# hw.net
KiCad netlist of a schematic drawn in EAGLE
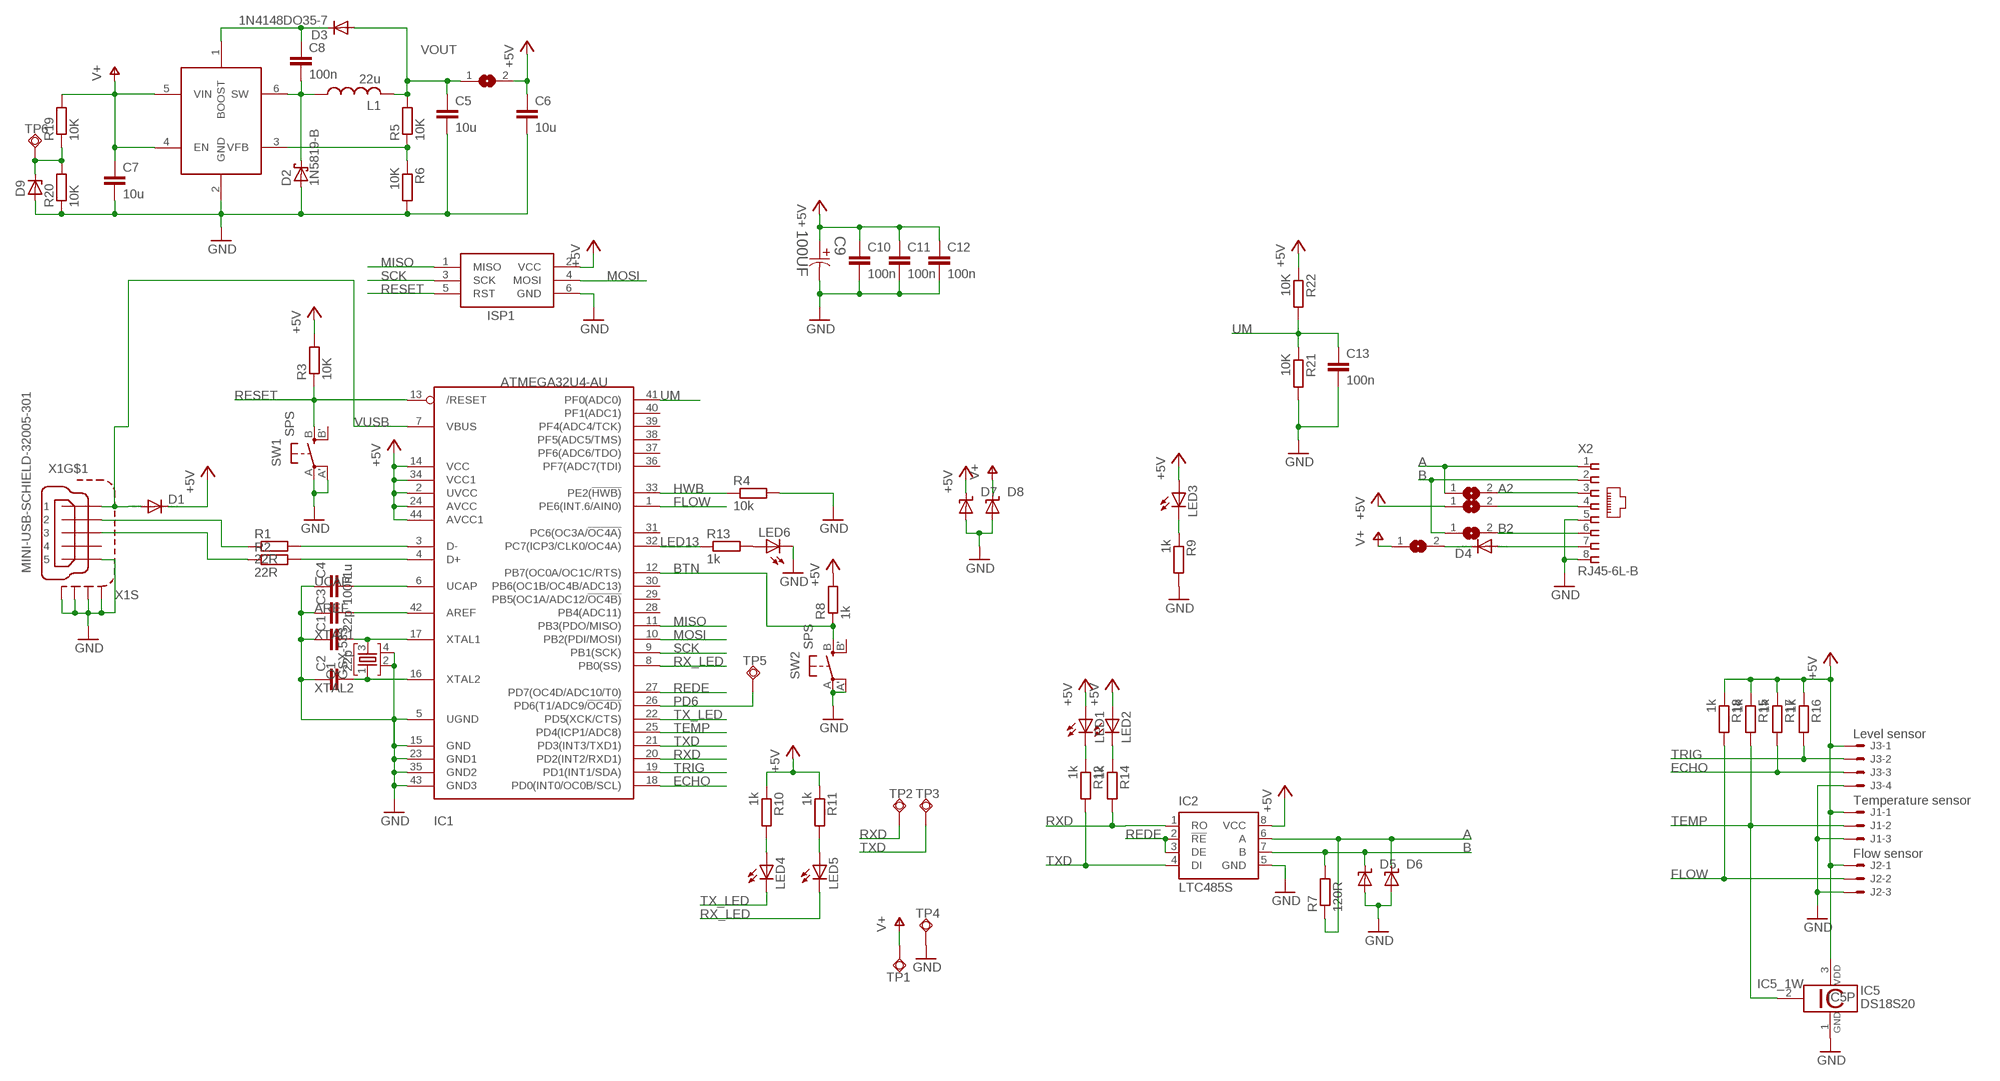
[diagram p0: schematic, sheet 1]

(export (version "E")
  (design (tool "Eeschema 10.0.6"))
  (components
    (comp (ref "C1")
      (value "22p")
      (footprint "eagle-import:C0805K")
      (libsource (lib "eagle-import") (part "C-EUC0805K"))
    )
    (comp (ref "C2")
      (value "22p")
      (footprint "eagle-import:C0805K")
      (libsource (lib "eagle-import") (part "C-EUC0805K"))
    )
    (comp (ref "C3")
      (value "100n")
      (footprint "eagle-import:C0805K")
      (libsource (lib "eagle-import") (part "C-EUC0805K"))
    )
    (comp (ref "C4")
      (value "1u")
      (footprint "eagle-import:C0805K")
      (libsource (lib "eagle-import") (part "C-EUC0805K"))
    )
    (comp (ref "C5")
      (value "10u")
      (footprint "eagle-import:C0805K")
      (libsource (lib "eagle-import") (part "C-EUC0805K"))
    )
    (comp (ref "C6")
      (value "10u")
      (footprint "eagle-import:C0805K")
      (libsource (lib "eagle-import") (part "C-EUC0805K"))
    )
    (comp (ref "C7")
      (value "10u")
      (footprint "eagle-import:C0805K")
      (libsource (lib "eagle-import") (part "rcl_334_C-EUC0805K"))
    )
    (comp (ref "C8")
      (value "100n")
      (footprint "eagle-import:C0805K")
      (libsource (lib "eagle-import") (part "C-EUC0805K"))
    )
    (comp (ref "C9")
      (value "100UF")
      (footprint "eagle-import:CAPAE660X610N")
      (fields (field (name "MPN") "EEE-FK0J101AP") (field (name "TOLERANCE") "±20 %"))
      (libsource (lib "eagle-import") (part "EEE--CASE-DFK0J101AP"))
    )
    (comp (ref "C10")
      (value "100n")
      (footprint "eagle-import:C0805K")
      (libsource (lib "eagle-import") (part "C-EUC0805K"))
    )
    (comp (ref "C11")
      (value "100n")
      (footprint "eagle-import:C0805K")
      (libsource (lib "eagle-import") (part "C-EUC0805K"))
    )
    (comp (ref "C12")
      (value "100n")
      (footprint "eagle-import:C0805K")
      (libsource (lib "eagle-import") (part "C-EUC0805K"))
    )
    (comp (ref "C13")
      (value "100n")
      (footprint "eagle-import:C0805K")
      (libsource (lib "eagle-import") (part "C-EUC0805K"))
    )
    (comp (ref "D1")
      (value "DIODE-MICROMELF-W")
      (footprint "eagle-import:MICROMELF-W")
      (libsource (lib "eagle-import") (part "DIODE-MICROMELF-W"))
    )
    (comp (ref "D2")
      (value "1N5819-B")
      (footprint "eagle-import:DO41-7.6")
      (libsource (lib "eagle-import") (part "1N5819-B"))
    )
    (comp (ref "D3")
      (value "1N4148DO35-7")
      (footprint "eagle-import:DO35-7")
      (libsource (lib "eagle-import") (part "1N4148DO35-7"))
    )
    (comp (ref "D4")
      (value "DIODE-MINIMELF")
      (footprint "eagle-import:MINIMELF")
      (libsource (lib "eagle-import") (part "diode_210_DIODE-MINIMELF"))
    )
    (comp (ref "D5")
      (value "SUPPRESSOR-SMBG")
      (footprint "eagle-import:SMBG")
      (libsource (lib "eagle-import") (part "SUPPRESSOR-SMBG"))
    )
    (comp (ref "D6")
      (value "SUPPRESSOR-SMBG")
      (footprint "eagle-import:SMBG")
      (libsource (lib "eagle-import") (part "SUPPRESSOR-SMBG"))
    )
    (comp (ref "D7")
      (value "SUPPRESSOR-SMBG")
      (footprint "eagle-import:SMBG")
      (libsource (lib "eagle-import") (part "SUPPRESSOR-SMBG"))
    )
    (comp (ref "D8")
      (value "SUPPRESSOR-SMBG")
      (footprint "eagle-import:SMBG")
      (libsource (lib "eagle-import") (part "SUPPRESSOR-SMBG"))
    )
    (comp (ref "D9")
      (value "ZENER-DIODESMB")
      (footprint "eagle-import:SMB")
      (libsource (lib "eagle-import") (part "ZENER-DIODESMB"))
    )
    (comp (ref "IC1")
      (value "ATMEGA32U4-AU")
      (footprint "eagle-import:TQFP44")
      (libsource (lib "eagle-import") (part "ATMEGA32U4-AU"))
    )
    (comp (ref "IC2")
      (value "LTC485S")
      (footprint "eagle-import:SOIC8")
      (libsource (lib "eagle-import") (part "LTC485S"))
    )
    (comp (ref "IC3")
      (value "MCP16301/H")
      (footprint "eagle-import:SOT23-6")
      (libsource (lib "eagle-import") (part "MCP16301/H"))
    )
    (comp (ref "IC5")
      (value "DS18S20")
      (footprint "eagle-import:TO92-")
      (fields (field (name "SPICEPREFIX") "X"))
      (libsource (lib "eagle-import") (part "DS18S20"))
    )
    (comp (ref "ISP1")
      (value "AVRISP-6")
      (footprint "eagle-import:AVRISP")
      (libsource (lib "eagle-import") (part "AVRISP-6"))
    )
    (comp (ref "J1")
      (value "Temperature sensor")
      (footprint "eagle-import:6410-03")
      (fields (field (name "MF") "MOLEX"))
      (libsource (lib "eagle-import") (part "22-?-0327-2031"))
    )
    (comp (ref "J2")
      (value "Flow sensor")
      (footprint "eagle-import:6410-03")
      (fields (field (name "MF") "MOLEX"))
      (libsource (lib "eagle-import") (part "22-?-0327-2031"))
    )
    (comp (ref "J3")
      (value "Level sensor")
      (footprint "eagle-import:6410-04")
      (fields (field (name "MF") "MOLEX"))
      (libsource (lib "eagle-import") (part "22-?-0427-2041"))
    )
    (comp (ref "L1")
      (value "22u")
      (footprint "eagle-import:0207_12")
      (libsource (lib "eagle-import") (part "L-US0207/12"))
    )
    (comp (ref "LED1")
      (value "LEDCHIPLED_0805")
      (footprint "eagle-import:CHIPLED_0805")
      (libsource (lib "eagle-import") (part "LEDCHIPLED_0805"))
    )
    (comp (ref "LED2")
      (value "LEDCHIPLED_0805")
      (footprint "eagle-import:CHIPLED_0805")
      (libsource (lib "eagle-import") (part "LEDCHIPLED_0805"))
    )
    (comp (ref "LED3")
      (value "LEDCHIPLED_0805")
      (footprint "eagle-import:CHIPLED_0805")
      (libsource (lib "eagle-import") (part "LEDCHIPLED_0805"))
    )
    (comp (ref "LED4")
      (value "LEDCHIPLED_0805")
      (footprint "eagle-import:CHIPLED_0805")
      (libsource (lib "eagle-import") (part "LEDCHIPLED_0805"))
    )
    (comp (ref "LED5")
      (value "LEDCHIPLED_0805")
      (footprint "eagle-import:CHIPLED_0805")
      (libsource (lib "eagle-import") (part "LEDCHIPLED_0805"))
    )
    (comp (ref "LED6")
      (value "LEDCHIPLED_0805")
      (footprint "eagle-import:CHIPLED_0805")
      (libsource (lib "eagle-import") (part "LEDCHIPLED_0805"))
    )
    (comp (ref "Q1")
      (value "GSX-533")
      (footprint "eagle-import:5032")
      (libsource (lib "eagle-import") (part "GSX-533"))
    )
    (comp (ref "R1")
      (value "22R")
      (footprint "eagle-import:M0805")
      (libsource (lib "eagle-import") (part "R-EU_M0805"))
    )
    (comp (ref "R2")
      (value "22R")
      (footprint "eagle-import:M0805")
      (libsource (lib "eagle-import") (part "R-EU_M0805"))
    )
    (comp (ref "R3")
      (value "10K")
      (footprint "eagle-import:M0805")
      (libsource (lib "eagle-import") (part "R-EU_M0805"))
    )
    (comp (ref "R4")
      (value "10k")
      (footprint "eagle-import:M0805")
      (libsource (lib "eagle-import") (part "R-EU_M0805"))
    )
    (comp (ref "R5")
      (value "10K")
      (footprint "eagle-import:M0805")
      (libsource (lib "eagle-import") (part "R-EU_M0805"))
    )
    (comp (ref "R6")
      (value "10K")
      (footprint "eagle-import:M0805")
      (libsource (lib "eagle-import") (part "R-EU_M0805"))
    )
    (comp (ref "R7")
      (value "120R")
      (footprint "eagle-import:M0805")
      (libsource (lib "eagle-import") (part "R-EU_M0805"))
    )
    (comp (ref "R8")
      (value "1k")
      (footprint "eagle-import:M0805")
      (libsource (lib "eagle-import") (part "R-EU_M0805"))
    )
    (comp (ref "R9")
      (value "1k")
      (footprint "eagle-import:M0805")
      (libsource (lib "eagle-import") (part "R-EU_M0805"))
    )
    (comp (ref "R10")
      (value "1k")
      (footprint "eagle-import:M0805")
      (libsource (lib "eagle-import") (part "R-EU_M0805"))
    )
    (comp (ref "R11")
      (value "1k")
      (footprint "eagle-import:M0805")
      (libsource (lib "eagle-import") (part "R-EU_M0805"))
    )
    (comp (ref "R12")
      (value "1k")
      (footprint "eagle-import:M0805")
      (libsource (lib "eagle-import") (part "R-EU_M0805"))
    )
    (comp (ref "R13")
      (value "1k")
      (footprint "eagle-import:M0805")
      (libsource (lib "eagle-import") (part "R-EU_M0805"))
    )
    (comp (ref "R14")
      (value "1k")
      (footprint "eagle-import:M0805")
      (libsource (lib "eagle-import") (part "R-EU_M0805"))
    )
    (comp (ref "R15")
      (value "1k")
      (footprint "eagle-import:M0805")
      (libsource (lib "eagle-import") (part "R-EU_M0805"))
    )
    (comp (ref "R16")
      (value "1k")
      (footprint "eagle-import:M0805")
      (libsource (lib "eagle-import") (part "R-EU_M0805"))
    )
    (comp (ref "R17")
      (value "1k")
      (footprint "eagle-import:M0805")
      (libsource (lib "eagle-import") (part "R-EU_M0805"))
    )
    (comp (ref "R18")
      (value "1k")
      (footprint "eagle-import:M0805")
      (libsource (lib "eagle-import") (part "R-EU_M0805"))
    )
    (comp (ref "R19")
      (value "10K")
      (footprint "eagle-import:M0805")
      (libsource (lib "eagle-import") (part "R-EU_M0805"))
    )
    (comp (ref "R20")
      (value "10K")
      (footprint "eagle-import:M0805")
      (libsource (lib "eagle-import") (part "R-EU_M0805"))
    )
    (comp (ref "R21")
      (value "10K")
      (footprint "eagle-import:M0805")
      (libsource (lib "eagle-import") (part "R-EU_M0805"))
    )
    (comp (ref "R22")
      (value "10K")
      (footprint "eagle-import:M0805")
      (libsource (lib "eagle-import") (part "R-EU_M0805"))
    )
    (comp (ref "SJ1") (value "SJ") (footprint "eagle-import:SJ") (libsource (lib "eagle-import") (part "SJ")))
    (comp (ref "SJ2") (value "SJ") (footprint "eagle-import:SJ") (libsource (lib "eagle-import") (part "SJ")))
    (comp (ref "SJ3") (value "SJ") (footprint "eagle-import:SJ") (libsource (lib "eagle-import") (part "SJ")))
    (comp (ref "SJ4") (value "SJ") (footprint "eagle-import:SJ") (libsource (lib "eagle-import") (part "SJ")))
    (comp (ref "SJ5") (value "SJ") (footprint "eagle-import:SJ") (libsource (lib "eagle-import") (part "SJ")))
    (comp (ref "SW1")
      (value "SPS")
      (footprint "eagle-import:EVQ-Q2")
      (libsource (lib "eagle-import") (part "SPST_TACT-EVQQ2"))
    )
    (comp (ref "SW2")
      (value "SPS")
      (footprint "eagle-import:EVQ-Q2")
      (libsource (lib "eagle-import") (part "SPST_TACT-EVQQ2"))
    )
    (comp (ref "TP1")
      (value "TPSQTP20SQ")
      (footprint "eagle-import:TP20SQ")
      (libsource (lib "eagle-import") (part "TPSQTP20SQ"))
    )
    (comp (ref "TP2")
      (value "TPSQTP20SQ")
      (footprint "eagle-import:TP20SQ")
      (libsource (lib "eagle-import") (part "TPSQTP20SQ"))
    )
    (comp (ref "TP3")
      (value "TPSQTP20SQ")
      (footprint "eagle-import:TP20SQ")
      (libsource (lib "eagle-import") (part "TPSQTP20SQ"))
    )
    (comp (ref "TP4")
      (value "TPSQTP20SQ")
      (footprint "eagle-import:TP20SQ")
      (libsource (lib "eagle-import") (part "TPSQTP20SQ"))
    )
    (comp (ref "TP5")
      (value "TPSQTP20SQ")
      (footprint "eagle-import:TP20SQ")
      (libsource (lib "eagle-import") (part "TPSQTP20SQ"))
    )
    (comp (ref "TP6")
      (value "TPSQTP20SQ")
      (footprint "eagle-import:TP20SQ")
      (libsource (lib "eagle-import") (part "TPSQTP20SQ"))
    )
    (comp (ref "X1")
      (value "MINI-USB-SCHIELD-32005-301")
      (footprint "eagle-import:32005-301")
      (libsource (lib "eagle-import") (part "MINI-USB-SCHIELD-32005-301"))
    )
    (comp (ref "X2")
      (value "RJ45-6L-B")
      (footprint "eagle-import:RJ45-NO-SHIELD")
      (libsource (lib "eagle-import") (part "RJ45-6L-B"))
    )
  )
  (nets
    (net (code "1") (name "+5V") (class "Default")
      (node (ref "C10") (pin "1") (pinfunction "1_1") (pintype "passive"))
      (node (ref "C11") (pin "1") (pinfunction "1_1") (pintype "passive"))
      (node (ref "C12") (pin "1") (pinfunction "1_1") (pintype "passive"))
      (node (ref "C6") (pin "1") (pinfunction "1_1") (pintype "passive"))
      (node (ref "C9") (pin "1") (pinfunction "1_1") (pintype "passive"))
      (node (ref "D1") (pin "C") (pinfunction "C_C") (pintype "passive"))
      (node (ref "D7") (pin "C") (pinfunction "C_C") (pintype "passive"))
      (node (ref "IC1") (pin "14") (pinfunction "VCC_14") (pintype "bidirectional"))
      (node (ref "IC1") (pin "2") (pinfunction "UVCC_2") (pintype "bidirectional"))
      (node (ref "IC1") (pin "24") (pinfunction "AVCC_24") (pintype "bidirectional"))
      (node (ref "IC1") (pin "34") (pinfunction "VCC1_34") (pintype "bidirectional"))
      (node (ref "IC1") (pin "44") (pinfunction "AVCC1_44") (pintype "bidirectional"))
      (node (ref "IC2") (pin "8") (pinfunction "VCC_8") (pintype "input"))
      (node (ref "IC5") (pin "3") (pinfunction "VDD_3") (pintype "power_in"))
      (node (ref "ISP1") (pin "2") (pinfunction "VCC_2") (pintype "power_in"))
      (node (ref "J1") (pin "1") (pinfunction "S_1") (pintype "passive"))
      (node (ref "J2") (pin "1") (pinfunction "S_1") (pintype "passive"))
      (node (ref "J3") (pin "1") (pinfunction "S_1") (pintype "passive"))
      (node (ref "LED1") (pin "A") (pinfunction "A_A") (pintype "passive"))
      (node (ref "LED2") (pin "A") (pinfunction "A_A") (pintype "passive"))
      (node (ref "LED3") (pin "A") (pinfunction "A_A") (pintype "passive"))
      (node (ref "R10") (pin "1") (pinfunction "1_1") (pintype "passive"))
      (node (ref "R11") (pin "1") (pinfunction "1_1") (pintype "passive"))
      (node (ref "R15") (pin "1") (pinfunction "1_1") (pintype "passive"))
      (node (ref "R16") (pin "1") (pinfunction "1_1") (pintype "passive"))
      (node (ref "R17") (pin "1") (pinfunction "1_1") (pintype "passive"))
      (node (ref "R18") (pin "1") (pinfunction "1_1") (pintype "passive"))
      (node (ref "R22") (pin "1") (pinfunction "1_1") (pintype "passive"))
      (node (ref "R3") (pin "2") (pinfunction "2_2") (pintype "passive"))
      (node (ref "R8") (pin "2") (pinfunction "2_2") (pintype "passive"))
      (node (ref "SJ4") (pin "1") (pinfunction "1_1") (pintype "passive"))
      (node (ref "SJ5") (pin "2") (pinfunction "2_2") (pintype "passive"))
    )
    (net (code "2") (name "/A") (class "Default")
      (node (ref "D6") (pin "C") (pinfunction "C_C") (pintype "passive"))
      (node (ref "IC2") (pin "6") (pinfunction "A_6") (pintype "bidirectional"))
      (node (ref "R7") (pin "1") (pinfunction "1_1") (pintype "passive"))
      (node (ref "SJ1") (pin "1") (pinfunction "1_1") (pintype "passive"))
      (node (ref "X2") (pin "1") (pinfunction "1_1") (pintype "passive"))
    )
    (net (code "3") (name "/A2") (class "Default")
      (node (ref "SJ1") (pin "2") (pinfunction "2_2") (pintype "passive"))
      (node (ref "X2") (pin "3") (pinfunction "3_3") (pintype "passive"))
    )
    (net (code "4") (name "/AREF") (class "Default")
      (node (ref "C3") (pin "2") (pinfunction "2_2") (pintype "passive"))
      (node (ref "IC1") (pin "42") (pinfunction "AREF_42") (pintype "bidirectional"))
    )
    (net (code "5") (name "/B") (class "Default")
      (node (ref "D5") (pin "C") (pinfunction "C_C") (pintype "passive"))
      (node (ref "IC2") (pin "7") (pinfunction "B_7") (pintype "bidirectional"))
      (node (ref "R7") (pin "2") (pinfunction "2_2") (pintype "passive"))
      (node (ref "SJ2") (pin "1") (pinfunction "1_1") (pintype "passive"))
      (node (ref "X2") (pin "2") (pinfunction "2_2") (pintype "passive"))
    )
    (net (code "6") (name "/B2") (class "Default")
      (node (ref "SJ2") (pin "2") (pinfunction "2_2") (pintype "passive"))
      (node (ref "X2") (pin "6") (pinfunction "6_6") (pintype "passive"))
    )
    (net (code "7") (name "/BTN") (class "Default")
      (node (ref "IC1") (pin "12") (pinfunction "PB7(OC0A/OC1C/RTS)_12") (pintype "bidirectional"))
      (node (ref "R8") (pin "1") (pinfunction "1_1") (pintype "passive"))
      (node (ref "SW2") (pin "B") (pinfunction "S_B") (pintype "passive"))
    )
    (net (code "8") (name "/ECHO") (class "Default")
      (node (ref "IC1") (pin "18") (pinfunction "PD0(INT0/OC0B/SCL)_18") (pintype "bidirectional"))
      (node (ref "J3") (pin "3") (pinfunction "S_3") (pintype "passive"))
      (node (ref "R17") (pin "2") (pinfunction "2_2") (pintype "passive"))
    )
    (net (code "9") (name "/FLOW") (class "Default")
      (node (ref "IC1") (pin "1") (pinfunction "PE6(INT.6/AIN0)_1") (pintype "bidirectional"))
      (node (ref "J2") (pin "2") (pinfunction "S_2") (pintype "passive"))
      (node (ref "R18") (pin "2") (pinfunction "2_2") (pintype "passive"))
    )
    (net (code "10") (name "/HWB") (class "Default")
      (node (ref "IC1") (pin "33") (pinfunction "PE2(~{HWB})_33") (pintype "bidirectional"))
      (node (ref "R4") (pin "1") (pinfunction "1_1") (pintype "passive"))
    )
    (net (code "11") (name "/LED13") (class "Default")
      (node (ref "IC1") (pin "32") (pinfunction "PC7(ICP3/CLK0/OC4A)_32") (pintype "bidirectional"))
      (node (ref "R13") (pin "1") (pinfunction "1_1") (pintype "passive"))
    )
    (net (code "12") (name "/MISO") (class "Default")
      (node (ref "IC1") (pin "11") (pinfunction "PB3(PDO/MISO)_11") (pintype "bidirectional"))
      (node (ref "ISP1") (pin "1") (pinfunction "MISO_1") (pintype "input"))
    )
    (net (code "13") (name "/MOSI") (class "Default")
      (node (ref "IC1") (pin "10") (pinfunction "PB2(PDI/MOSI)_10") (pintype "bidirectional"))
      (node (ref "ISP1") (pin "4") (pinfunction "MOSI_4") (pintype "output"))
    )
    (net (code "14") (name "/PD6") (class "Default")
      (node (ref "IC1") (pin "26") (pinfunction "PD6(T1/ADC9/~{OC4D})_26") (pintype "bidirectional"))
      (node (ref "TP5") (pin "TP") (pinfunction "TP_TP") (pintype "input"))
    )
    (net (code "15") (name "/REDE") (class "Default")
      (node (ref "IC1") (pin "27") (pinfunction "PD7(OC4D/ADC10/T0)_27") (pintype "bidirectional"))
      (node (ref "IC2") (pin "2") (pinfunction "~{RE}_2") (pintype "input"))
      (node (ref "IC2") (pin "3") (pinfunction "DE_3") (pintype "input"))
    )
    (net (code "16") (name "/RESET") (class "Default")
      (node (ref "IC1") (pin "13") (pinfunction "/RESET_13") (pintype "bidirectional"))
      (node (ref "ISP1") (pin "5") (pinfunction "RST_5") (pintype "output"))
      (node (ref "R3") (pin "1") (pinfunction "1_1") (pintype "passive"))
      (node (ref "SW1") (pin "B") (pinfunction "S_B") (pintype "passive"))
    )
    (net (code "17") (name "/RXD") (class "Default")
      (node (ref "IC1") (pin "20") (pinfunction "PD2(INT2/RXD1)_20") (pintype "bidirectional"))
      (node (ref "IC2") (pin "1") (pinfunction "RO_1") (pintype "output"))
      (node (ref "R14") (pin "2") (pinfunction "2_2") (pintype "passive"))
      (node (ref "TP2") (pin "TP") (pinfunction "TP_TP") (pintype "input"))
    )
    (net (code "18") (name "/RX_LED") (class "Default")
      (node (ref "IC1") (pin "8") (pinfunction "PB0(SS)_8") (pintype "bidirectional"))
      (node (ref "LED5") (pin "C") (pinfunction "C_C") (pintype "passive"))
    )
    (net (code "19") (name "/SCK") (class "Default")
      (node (ref "IC1") (pin "9") (pinfunction "PB1(SCK)_9") (pintype "bidirectional"))
      (node (ref "ISP1") (pin "3") (pinfunction "SCK_3") (pintype "output"))
    )
    (net (code "20") (name "/TEMP") (class "Default")
      (node (ref "IC1") (pin "25") (pinfunction "PD4(ICP1/ADC8)_25") (pintype "bidirectional"))
      (node (ref "IC5") (pin "2") (pinfunction "1W_2") (pintype "power_in"))
      (node (ref "J1") (pin "2") (pinfunction "S_2") (pintype "passive"))
      (node (ref "R15") (pin "2") (pinfunction "2_2") (pintype "passive"))
    )
    (net (code "21") (name "/TRIG") (class "Default")
      (node (ref "IC1") (pin "19") (pinfunction "PD1(INT1/SDA)_19") (pintype "bidirectional"))
      (node (ref "J3") (pin "2") (pinfunction "S_2") (pintype "passive"))
      (node (ref "R16") (pin "2") (pinfunction "2_2") (pintype "passive"))
    )
    (net (code "22") (name "/TXD") (class "Default")
      (node (ref "IC1") (pin "21") (pinfunction "PD3(INT3/TXD1)_21") (pintype "bidirectional"))
      (node (ref "IC2") (pin "4") (pinfunction "DI_4") (pintype "input"))
      (node (ref "R12") (pin "2") (pinfunction "2_2") (pintype "passive"))
      (node (ref "TP3") (pin "TP") (pinfunction "TP_TP") (pintype "input"))
    )
    (net (code "23") (name "/TX_LED") (class "Default")
      (node (ref "IC1") (pin "22") (pinfunction "PD5(XCK/CTS)_22") (pintype "bidirectional"))
      (node (ref "LED4") (pin "C") (pinfunction "C_C") (pintype "passive"))
    )
    (net (code "24") (name "/UCAP") (class "Default")
      (node (ref "C4") (pin "2") (pinfunction "2_2") (pintype "passive"))
      (node (ref "IC1") (pin "6") (pinfunction "UCAP_6") (pintype "bidirectional"))
    )
    (net (code "25") (name "/UM") (class "Default")
      (node (ref "C13") (pin "1") (pinfunction "1_1") (pintype "passive"))
      (node (ref "IC1") (pin "41") (pinfunction "PF0(ADC0)_41") (pintype "bidirectional"))
      (node (ref "R21") (pin "1") (pinfunction "1_1") (pintype "passive"))
      (node (ref "R22") (pin "2") (pinfunction "2_2") (pintype "passive"))
    )
    (net (code "26") (name "/VOUT") (class "Default")
      (node (ref "C5") (pin "1") (pinfunction "1_1") (pintype "passive"))
      (node (ref "D3") (pin "A") (pinfunction "A_A") (pintype "passive"))
      (node (ref "L1") (pin "2") (pinfunction "2_2") (pintype "passive"))
      (node (ref "R5") (pin "2") (pinfunction "2_2") (pintype "passive"))
      (node (ref "SJ5") (pin "1") (pinfunction "1_1") (pintype "passive"))
    )
    (net (code "27") (name "/VUSB") (class "Default")
      (node (ref "D1") (pin "A") (pinfunction "A_A") (pintype "passive"))
      (node (ref "IC1") (pin "7") (pinfunction "VBUS_7") (pintype "bidirectional"))
      (node (ref "X1") (pin "1") (pinfunction "1_1") (pintype "passive"))
    )
    (net (code "28") (name "/XTAL1") (class "Default")
      (node (ref "C1") (pin "2") (pinfunction "2_2") (pintype "passive"))
      (node (ref "IC1") (pin "17") (pinfunction "XTAL1_17") (pintype "bidirectional"))
      (node (ref "Q1") (pin "3") (pinfunction "XTAL2_3") (pintype "passive"))
    )
    (net (code "29") (name "/XTAL2") (class "Default")
      (node (ref "C2") (pin "2") (pinfunction "2_2") (pintype "passive"))
      (node (ref "IC1") (pin "16") (pinfunction "XTAL2_16") (pintype "bidirectional"))
      (node (ref "Q1") (pin "1") (pinfunction "XTAL1_1") (pintype "passive"))
    )
    (net (code "30") (name "GND") (class "Default")
      (node (ref "C1") (pin "1") (pinfunction "1_1") (pintype "passive"))
      (node (ref "C10") (pin "2") (pinfunction "2_2") (pintype "passive"))
      (node (ref "C11") (pin "2") (pinfunction "2_2") (pintype "passive"))
      (node (ref "C12") (pin "2") (pinfunction "2_2") (pintype "passive"))
      (node (ref "C13") (pin "2") (pinfunction "2_2") (pintype "passive"))
      (node (ref "C2") (pin "1") (pinfunction "1_1") (pintype "passive"))
      (node (ref "C3") (pin "1") (pinfunction "1_1") (pintype "passive"))
      (node (ref "C4") (pin "1") (pinfunction "1_1") (pintype "passive"))
      (node (ref "C5") (pin "2") (pinfunction "2_2") (pintype "passive"))
      (node (ref "C6") (pin "2") (pinfunction "2_2") (pintype "passive"))
      (node (ref "C7") (pin "2") (pinfunction "2_2") (pintype "passive"))
      (node (ref "C9") (pin "2") (pinfunction "2_2") (pintype "passive"))
      (node (ref "D2") (pin "A") (pinfunction "A_A") (pintype "passive"))
      (node (ref "D5") (pin "A") (pinfunction "A_A") (pintype "passive"))
      (node (ref "D6") (pin "A") (pinfunction "A_A") (pintype "passive"))
      (node (ref "D7") (pin "A") (pinfunction "A_A") (pintype "passive"))
      (node (ref "D8") (pin "A") (pinfunction "A_A") (pintype "passive"))
      (node (ref "D9") (pin "A") (pinfunction "A_A") (pintype "passive"))
      (node (ref "IC1") (pin "15") (pinfunction "GND_15") (pintype "bidirectional"))
      (node (ref "IC1") (pin "23") (pinfunction "GND1_23") (pintype "bidirectional"))
      (node (ref "IC1") (pin "35") (pinfunction "GND2_35") (pintype "bidirectional"))
      (node (ref "IC1") (pin "43") (pinfunction "GND3_43") (pintype "bidirectional"))
      (node (ref "IC1") (pin "5") (pinfunction "UGND_5") (pintype "bidirectional"))
      (node (ref "IC2") (pin "5") (pinfunction "GND_5") (pintype "input"))
      (node (ref "IC3") (pin "2") (pinfunction "GND_2") (pintype "power_in"))
      (node (ref "IC5") (pin "1") (pinfunction "GND_1") (pintype "power_in"))
      (node (ref "ISP1") (pin "6") (pinfunction "GND_6") (pintype "power_in"))
      (node (ref "J1") (pin "3") (pinfunction "S_3") (pintype "passive"))
      (node (ref "J2") (pin "3") (pinfunction "S_3") (pintype "passive"))
      (node (ref "J3") (pin "4") (pinfunction "S_4") (pintype "passive"))
      (node (ref "LED6") (pin "C") (pinfunction "C_C") (pintype "passive"))
      (node (ref "Q1") (pin "2") (pinfunction "GND1_2") (pintype "passive"))
      (node (ref "Q1") (pin "4") (pinfunction "GND2_4") (pintype "passive"))
      (node (ref "R20") (pin "1") (pinfunction "1_1") (pintype "passive"))
      (node (ref "R21") (pin "2") (pinfunction "2_2") (pintype "passive"))
      (node (ref "R4") (pin "2") (pinfunction "2_2") (pintype "passive"))
      (node (ref "R6") (pin "2") (pinfunction "2_2") (pintype "passive"))
      (node (ref "R9") (pin "2") (pinfunction "2_2") (pintype "passive"))
      (node (ref "SW1") (pin "A") (pinfunction "P_A") (pintype "passive"))
      (node (ref "SW1") (pin "A'") (pinfunction "P1_A'") (pintype "passive"))
      (node (ref "SW2") (pin "A") (pinfunction "P_A") (pintype "passive"))
      (node (ref "SW2") (pin "A'") (pinfunction "P1_A'") (pintype "passive"))
      (node (ref "TP4") (pin "TP") (pinfunction "TP_TP") (pintype "input"))
      (node (ref "X1") (pin "5") (pinfunction "5_5") (pintype "passive"))
      (node (ref "X1") (pin "M1") (pinfunction "S1_M1") (pintype "passive"))
      (node (ref "X1") (pin "M2") (pinfunction "S2_M2") (pintype "passive"))
      (node (ref "X1") (pin "M3") (pinfunction "S3_M3") (pintype "passive"))
      (node (ref "X1") (pin "M4") (pinfunction "S4_M4") (pintype "passive"))
      (node (ref "X2") (pin "5") (pinfunction "5_5") (pintype "passive"))
      (node (ref "X2") (pin "8") (pinfunction "8_8") (pintype "passive"))
    )
    (net (code "31") (name "Net-(D4-PadA)") (class "Default")
      (node (ref "D4") (pin "A") (pinfunction "A_A") (pintype "passive"))
      (node (ref "X2") (pin "7") (pinfunction "7_7") (pintype "passive"))
    )
    (net (code "32") (name "Net-(D4-PadC)") (class "Default")
      (node (ref "D4") (pin "C") (pinfunction "C_C") (pintype "passive"))
      (node (ref "SJ3") (pin "2") (pinfunction "2_2") (pintype "passive"))
    )
    (net (code "33") (name "Net-(D9-PadC)") (class "Default")
      (node (ref "D9") (pin "C") (pinfunction "C_C") (pintype "passive"))
      (node (ref "R19") (pin "1") (pinfunction "1_1") (pintype "passive"))
      (node (ref "R20") (pin "2") (pinfunction "2_2") (pintype "passive"))
      (node (ref "TP6") (pin "TP") (pinfunction "TP_TP") (pintype "input"))
    )
    (net (code "34") (name "Net-(IC1-D+)") (class "Default")
      (node (ref "IC1") (pin "4") (pinfunction "D+_4") (pintype "bidirectional"))
      (node (ref "R2") (pin "2") (pinfunction "2_2") (pintype "passive"))
    )
    (net (code "35") (name "Net-(IC1-D-)") (class "Default")
      (node (ref "IC1") (pin "3") (pinfunction "D-_3") (pintype "bidirectional"))
      (node (ref "R1") (pin "2") (pinfunction "2_2") (pintype "passive"))
    )
    (net (code "36") (name "Net-(IC3-BOOST)") (class "Default")
      (node (ref "C8") (pin "1") (pinfunction "1_1") (pintype "passive"))
      (node (ref "D3") (pin "C") (pinfunction "C_C") (pintype "passive"))
      (node (ref "IC3") (pin "1") (pinfunction "BOOST_1") (pintype "bidirectional"))
    )
    (net (code "37") (name "Net-(IC3-SW)") (class "Default")
      (node (ref "C8") (pin "2") (pinfunction "2_2") (pintype "passive"))
      (node (ref "D2") (pin "C") (pinfunction "C_C") (pintype "passive"))
      (node (ref "IC3") (pin "6") (pinfunction "SW_6") (pintype "power_in"))
      (node (ref "L1") (pin "1") (pinfunction "1_1") (pintype "passive"))
    )
    (net (code "38") (name "Net-(IC3-VFB)") (class "Default")
      (node (ref "IC3") (pin "3") (pinfunction "VFB_3") (pintype "bidirectional"))
      (node (ref "R5") (pin "1") (pinfunction "1_1") (pintype "passive"))
      (node (ref "R6") (pin "1") (pinfunction "1_1") (pintype "passive"))
    )
    (net (code "39") (name "Net-(LED1-PadC)") (class "Default")
      (node (ref "LED1") (pin "C") (pinfunction "C_C") (pintype "passive"))
      (node (ref "R12") (pin "1") (pinfunction "1_1") (pintype "passive"))
    )
    (net (code "40") (name "Net-(LED2-PadC)") (class "Default")
      (node (ref "LED2") (pin "C") (pinfunction "C_C") (pintype "passive"))
      (node (ref "R14") (pin "1") (pinfunction "1_1") (pintype "passive"))
    )
    (net (code "41") (name "Net-(LED3-PadC)") (class "Default")
      (node (ref "LED3") (pin "C") (pinfunction "C_C") (pintype "passive"))
      (node (ref "R9") (pin "1") (pinfunction "1_1") (pintype "passive"))
    )
    (net (code "42") (name "Net-(LED4-PadA)") (class "Default")
      (node (ref "LED4") (pin "A") (pinfunction "A_A") (pintype "passive"))
      (node (ref "R10") (pin "2") (pinfunction "2_2") (pintype "passive"))
    )
    (net (code "43") (name "Net-(LED5-PadA)") (class "Default")
      (node (ref "LED5") (pin "A") (pinfunction "A_A") (pintype "passive"))
      (node (ref "R11") (pin "2") (pinfunction "2_2") (pintype "passive"))
    )
    (net (code "44") (name "Net-(LED6-PadA)") (class "Default")
      (node (ref "LED6") (pin "A") (pinfunction "A_A") (pintype "passive"))
      (node (ref "R13") (pin "2") (pinfunction "2_2") (pintype "passive"))
    )
    (net (code "45") (name "Net-(R1-Pad1)") (class "Default")
      (node (ref "R1") (pin "1") (pinfunction "1_1") (pintype "passive"))
      (node (ref "X1") (pin "2") (pinfunction "2_2") (pintype "passive"))
    )
    (net (code "46") (name "Net-(R2-Pad1)") (class "Default")
      (node (ref "R2") (pin "1") (pinfunction "1_1") (pintype "passive"))
      (node (ref "X1") (pin "3") (pinfunction "3_3") (pintype "passive"))
    )
    (net (code "47") (name "Net-(SJ4-Pad2)") (class "Default")
      (node (ref "SJ4") (pin "2") (pinfunction "2_2") (pintype "passive"))
      (node (ref "X2") (pin "4") (pinfunction "4_4") (pintype "passive"))
    )
    (net (code "48") (name "V+") (class "Default")
      (node (ref "C7") (pin "1") (pinfunction "1_1") (pintype "passive"))
      (node (ref "D8") (pin "C") (pinfunction "C_C") (pintype "passive"))
      (node (ref "IC3") (pin "4") (pinfunction "EN_4") (pintype "bidirectional"))
      (node (ref "IC3") (pin "5") (pinfunction "VIN_5") (pintype "power_in"))
      (node (ref "R19") (pin "2") (pinfunction "2_2") (pintype "passive"))
      (node (ref "SJ3") (pin "1") (pinfunction "1_1") (pintype "passive"))
      (node (ref "TP1") (pin "TP") (pinfunction "TP_TP") (pintype "input"))
    )
    (net (code "49") (name "unconnected-(IC1-PB4(ADC11)-Pad28)") (class "Default")
      (node (ref "IC1") (pin "28") (pinfunction "PB4(ADC11)_28") (pintype "bidirectional"))
    )
    (net (code "50") (name "unconnected-(IC1-PB5(OC1A{slash}ADC12{slash}~{OC4B})-Pad29)") (class "Default")
      (node (ref "IC1") (pin "29") (pinfunction "PB5(OC1A/ADC12/~{OC4B})_29") (pintype "bidirectional"))
    )
    (net (code "51") (name "unconnected-(IC1-PB6(OC1B{slash}OC4B{slash}ADC13)-Pad30)") (class "Default")
      (node (ref "IC1") (pin "30") (pinfunction "PB6(OC1B/OC4B/ADC13)_30") (pintype "bidirectional"))
    )
    (net (code "52") (name "unconnected-(IC1-PC6(OC3A{slash}~{OC4A})-Pad31)") (class "Default")
      (node (ref "IC1") (pin "31") (pinfunction "PC6(OC3A/~{OC4A})_31") (pintype "bidirectional"))
    )
    (net (code "53") (name "unconnected-(IC1-PF1(ADC1)-Pad40)") (class "Default")
      (node (ref "IC1") (pin "40") (pinfunction "PF1(ADC1)_40") (pintype "bidirectional"))
    )
    (net (code "54") (name "unconnected-(IC1-PF4(ADC4{slash}TCK)-Pad39)") (class "Default")
      (node (ref "IC1") (pin "39") (pinfunction "PF4(ADC4/TCK)_39") (pintype "bidirectional"))
    )
    (net (code "55") (name "unconnected-(IC1-PF5(ADC5{slash}TMS)-Pad38)") (class "Default")
      (node (ref "IC1") (pin "38") (pinfunction "PF5(ADC5/TMS)_38") (pintype "bidirectional"))
    )
    (net (code "56") (name "unconnected-(IC1-PF6(ADC6{slash}TDO)-Pad37)") (class "Default")
      (node (ref "IC1") (pin "37") (pinfunction "PF6(ADC6/TDO)_37") (pintype "bidirectional"))
    )
    (net (code "57") (name "unconnected-(IC1-PF7(ADC7(TDI)-Pad36)") (class "Default")
      (node (ref "IC1") (pin "36") (pinfunction "PF7(ADC7(TDI)_36") (pintype "bidirectional"))
    )
    (net (code "58") (name "unconnected-(SW1-S1-PadB')") (class "Default")
      (node (ref "SW1") (pin "B'") (pinfunction "S1_B'") (pintype "passive"))
    )
    (net (code "59") (name "unconnected-(SW2-S1-PadB')") (class "Default")
      (node (ref "SW2") (pin "B'") (pinfunction "S1_B'") (pintype "passive"))
    )
    (net (code "60") (name "unconnected-(X1-Pad4)") (class "Default")
      (node (ref "X1") (pin "4") (pinfunction "4_4") (pintype "passive"))
    )
  )
)
